# v1_2.net
KiCad netlist of a schematic drawn in EAGLE
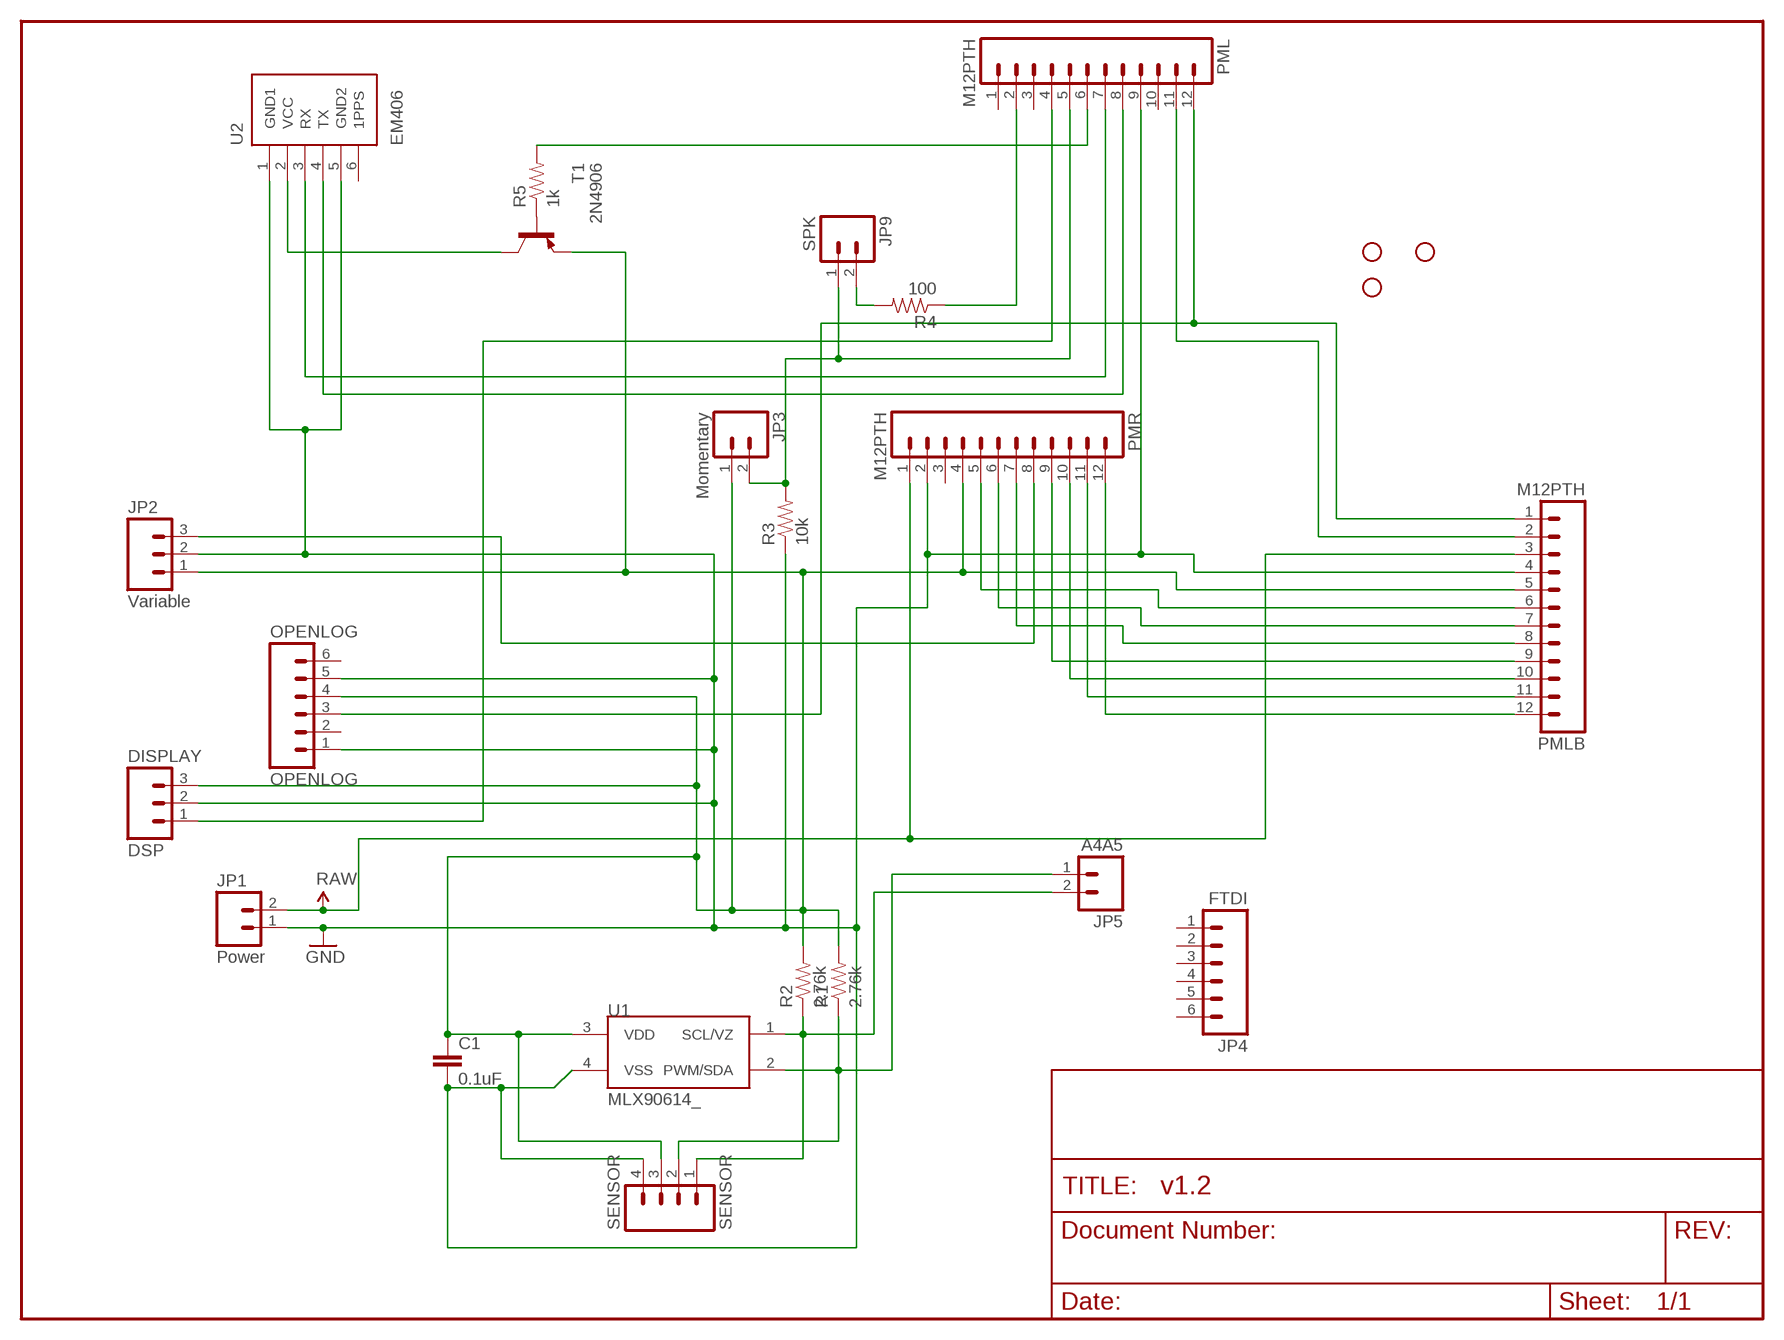
[diagram p0: schematic, sheet 1]

(export (version "E")
  (design (tool "Eeschema 10.0.6"))
  (components
    (comp (ref "2N4906")
      (value "T1")
      (footprint "eagle-import:TO92-EBC")
      (libsource (lib "eagle-import") (part "-PNP-TO92-EBC2N3906"))
    )
    (comp (ref "C1")
      (value "0.1uF")
      (footprint "eagle-import:CAP-PTH-LARGE")
      (libsource (lib "eagle-import") (part "CAPPTH3"))
    )
    (comp (ref "DISPLAY")
      (value "DSP")
      (footprint "eagle-import:SCREWTERMINAL-3.5MM-3_LOCK.007S")
      (libsource (lib "eagle-import") (part "M03SCREW_LOCK"))
    )
    (comp (ref "JP1")
      (value "Power")
      (footprint "eagle-import:JST-2-PTH")
      (libsource (lib "eagle-import") (part "M02JST-PTH-2"))
    )
    (comp (ref "JP2")
      (value "Variable")
      (footprint "eagle-import:SCREWTERMINAL-3.5MM-3_LOCK.007S")
      (libsource (lib "eagle-import") (part "M03SCREW_LOCK"))
    )
    (comp (ref "JP3")
      (value "Momentary")
      (footprint "eagle-import:JST-2-PTH")
      (libsource (lib "eagle-import") (part "M02JST-PTH-2"))
    )
    (comp (ref "JP4")
      (value "FTDI")
      (footprint "eagle-import:1X06")
      (libsource (lib "eagle-import") (part "M06SIP"))
    )
    (comp (ref "JP5")
      (value "A4A5")
      (footprint "eagle-import:1X02")
      (libsource (lib "eagle-import") (part "M02PTH"))
    )
    (comp (ref "JP6")
      (value "STAND-OFFTIGHT")
      (footprint "eagle-import:STAND-OFF-TIGHT")
      (libsource (lib "eagle-import") (part "STAND-OFFTIGHT"))
    )
    (comp (ref "JP7")
      (value "STAND-OFFTIGHT")
      (footprint "eagle-import:STAND-OFF-TIGHT")
      (libsource (lib "eagle-import") (part "STAND-OFFTIGHT"))
    )
    (comp (ref "JP8")
      (value "STAND-OFFTIGHT")
      (footprint "eagle-import:STAND-OFF-TIGHT")
      (libsource (lib "eagle-import") (part "STAND-OFFTIGHT"))
    )
    (comp (ref "JP9")
      (value "SPK")
      (footprint "eagle-import:SCREWTERMINAL-3.5MM-2")
      (libsource (lib "eagle-import") (part "M023.5MM"))
    )
    (comp (ref "OPENLOG")
      (value "OPENLOG")
      (footprint "eagle-import:1X06_LOCK")
      (libsource (lib "eagle-import") (part "M06LOCK"))
    )
    (comp (ref "PML")
      (value "M12PTH")
      (footprint "eagle-import:1X12")
      (libsource (lib "eagle-import") (part "M12PTH"))
    )
    (comp (ref "PMLB")
      (value "M12PTH")
      (footprint "eagle-import:1X12")
      (libsource (lib "eagle-import") (part "M12PTH"))
    )
    (comp (ref "PMR")
      (value "M12PTH")
      (footprint "eagle-import:1X12")
      (libsource (lib "eagle-import") (part "M12PTH"))
    )
    (comp (ref "R1")
      (value "2.76k")
      (footprint "eagle-import:AXIAL-0.4")
      (libsource (lib "eagle-import") (part "RESISTORPTH-1/4W"))
    )
    (comp (ref "R2")
      (value "2.76k")
      (footprint "eagle-import:AXIAL-0.4")
      (libsource (lib "eagle-import") (part "RESISTORPTH-1/4W"))
    )
    (comp (ref "R3")
      (value "10k")
      (footprint "eagle-import:AXIAL-0.4")
      (libsource (lib "eagle-import") (part "RESISTORPTH-1/4W"))
    )
    (comp (ref "R4")
      (value "100")
      (footprint "eagle-import:AXIAL-0.4")
      (libsource (lib "eagle-import") (part "RESISTORPTH-1/4W"))
    )
    (comp (ref "R5")
      (value "1k")
      (footprint "eagle-import:AXIAL-0.4")
      (libsource (lib "eagle-import") (part "RESISTORPTH-1/4W"))
    )
    (comp (ref "SENSOR")
      (value "SENSOR")
      (footprint "eagle-import:SCREWTERMINAL-3.5MM-4_LOCK")
      (libsource (lib "eagle-import") (part "M04SCREW_LOCK"))
    )
    (comp (ref "U1")
      (value "MLX90614_")
      (footprint "eagle-import:TO-39")
      (libsource (lib "eagle-import") (part "MLX90614_"))
    )
    (comp (ref "U2")
      (value "EM406")
      (footprint "eagle-import:EM406")
      (libsource (lib "eagle-import") (part "EM406"))
    )
  )
  (nets
    (net (code "1") (name "GND") (class "Default")
      (node (ref "C1") (pin "2") (pinfunction "2_2") (pintype "passive"))
      (node (ref "DISPLAY") (pin "2") (pinfunction "2_2") (pintype "passive"))
      (node (ref "JP1") (pin "1") (pinfunction "1_1") (pintype "passive"))
      (node (ref "JP2") (pin "2") (pinfunction "2_2") (pintype "passive"))
      (node (ref "OPENLOG") (pin "1") (pinfunction "1_1") (pintype "passive"))
      (node (ref "OPENLOG") (pin "5") (pinfunction "5_5") (pintype "passive"))
      (node (ref "PML") (pin "9") (pinfunction "9_9") (pintype "passive"))
      (node (ref "PMLB") (pin "4") (pinfunction "4_4") (pintype "passive"))
      (node (ref "PMR") (pin "2") (pinfunction "2_2") (pintype "passive"))
      (node (ref "R3") (pin "P$1") (pinfunction "1_P$1") (pintype "passive"))
      (node (ref "SENSOR") (pin "4") (pinfunction "4_4") (pintype "passive"))
      (node (ref "U1") (pin "4") (pinfunction "VSS_4") (pintype "bidirectional"))
      (node (ref "U2") (pin "1") (pinfunction "GND1_1") (pintype "bidirectional"))
      (node (ref "U2") (pin "5") (pinfunction "GND2_5") (pintype "bidirectional"))
    )
    (net (code "2") (name "Net-(DISPLAY-Pad1)") (class "Default")
      (node (ref "DISPLAY") (pin "1") (pinfunction "1_1") (pintype "passive"))
      (node (ref "PML") (pin "4") (pinfunction "4_4") (pintype "passive"))
    )
    (net (code "3") (name "Net-(JP2-Pad3)") (class "Default")
      (node (ref "JP2") (pin "3") (pinfunction "3_3") (pintype "passive"))
      (node (ref "PMR") (pin "8") (pinfunction "8_8") (pintype "passive"))
    )
    (net (code "4") (name "Net-(OPENLOG-Pad3)") (class "Default")
      (node (ref "OPENLOG") (pin "3") (pinfunction "3_3") (pintype "passive"))
      (node (ref "PML") (pin "12") (pinfunction "12_12") (pintype "passive"))
      (node (ref "PMLB") (pin "1") (pinfunction "1_1") (pintype "passive"))
    )
    (net (code "5") (name "Net-(PML-Pad11)") (class "Default")
      (node (ref "PML") (pin "11") (pinfunction "11_11") (pintype "passive"))
      (node (ref "PMLB") (pin "2") (pinfunction "2_2") (pintype "passive"))
    )
    (net (code "6") (name "Net-(PMLB-Pad6)") (class "Default")
      (node (ref "PMLB") (pin "6") (pinfunction "6_6") (pintype "passive"))
      (node (ref "PMR") (pin "5") (pinfunction "5_5") (pintype "passive"))
    )
    (net (code "7") (name "Net-(PMLB-Pad7)") (class "Default")
      (node (ref "PMLB") (pin "7") (pinfunction "7_7") (pintype "passive"))
      (node (ref "PMR") (pin "6") (pinfunction "6_6") (pintype "passive"))
    )
    (net (code "8") (name "Net-(PMLB-Pad8)") (class "Default")
      (node (ref "PMLB") (pin "8") (pinfunction "8_8") (pintype "passive"))
      (node (ref "PMR") (pin "7") (pinfunction "7_7") (pintype "passive"))
    )
    (net (code "9") (name "Net-(PMLB-Pad9)") (class "Default")
      (node (ref "PMLB") (pin "9") (pinfunction "9_9") (pintype "passive"))
      (node (ref "PMR") (pin "9") (pinfunction "9_9") (pintype "passive"))
    )
    (net (code "10") (name "Net-(PMLB-Pad10)") (class "Default")
      (node (ref "PMLB") (pin "10") (pinfunction "10_10") (pintype "passive"))
      (node (ref "PMR") (pin "10") (pinfunction "10_10") (pintype "passive"))
    )
    (net (code "11") (name "Net-(PMLB-Pad11)") (class "Default")
      (node (ref "PMLB") (pin "11") (pinfunction "11_11") (pintype "passive"))
      (node (ref "PMR") (pin "11") (pinfunction "11_11") (pintype "passive"))
    )
    (net (code "12") (name "Net-(PMLB-Pad12)") (class "Default")
      (node (ref "PMLB") (pin "12") (pinfunction "12_12") (pintype "passive"))
      (node (ref "PMR") (pin "12") (pinfunction "12_12") (pintype "passive"))
    )
    (net (code "13") (name "Net-(R1-1)") (class "Default")
      (node (ref "JP5") (pin "1") (pinfunction "1_1") (pintype "passive"))
      (node (ref "R1") (pin "P$1") (pinfunction "1_P$1") (pintype "passive"))
      (node (ref "SENSOR") (pin "2") (pinfunction "2_2") (pintype "passive"))
      (node (ref "U1") (pin "2") (pinfunction "PWM/SDA_2") (pintype "bidirectional"))
    )
    (net (code "14") (name "Net-(R1-2)") (class "Default")
      (node (ref "2N4906") (pin "E") (pinfunction "E_E") (pintype "passive"))
      (node (ref "C1") (pin "1") (pinfunction "1_1") (pintype "passive"))
      (node (ref "DISPLAY") (pin "3") (pinfunction "3_3") (pintype "passive"))
      (node (ref "JP2") (pin "1") (pinfunction "1_1") (pintype "passive"))
      (node (ref "JP3") (pin "1") (pinfunction "1_1") (pintype "passive"))
      (node (ref "OPENLOG") (pin "4") (pinfunction "4_4") (pintype "passive"))
      (node (ref "PMLB") (pin "5") (pinfunction "5_5") (pintype "passive"))
      (node (ref "PMR") (pin "4") (pinfunction "4_4") (pintype "passive"))
      (node (ref "R1") (pin "P$2") (pinfunction "2_P$2") (pintype "passive"))
      (node (ref "R2") (pin "P$2") (pinfunction "2_P$2") (pintype "passive"))
      (node (ref "SENSOR") (pin "3") (pinfunction "3_3") (pintype "passive"))
      (node (ref "U1") (pin "3") (pinfunction "VDD_3") (pintype "bidirectional"))
    )
    (net (code "15") (name "Net-(R2-1)") (class "Default")
      (node (ref "JP5") (pin "2") (pinfunction "2_2") (pintype "passive"))
      (node (ref "R2") (pin "P$1") (pinfunction "1_P$1") (pintype "passive"))
      (node (ref "SENSOR") (pin "1") (pinfunction "1_1") (pintype "passive"))
      (node (ref "U1") (pin "1") (pinfunction "SCL/VZ_1") (pintype "bidirectional"))
    )
    (net (code "16") (name "Net-(R3-2)") (class "Default")
      (node (ref "JP3") (pin "2") (pinfunction "2_2") (pintype "passive"))
      (node (ref "JP9") (pin "1") (pinfunction "1_1") (pintype "passive"))
      (node (ref "PML") (pin "5") (pinfunction "5_5") (pintype "passive"))
      (node (ref "R3") (pin "P$2") (pinfunction "2_P$2") (pintype "passive"))
    )
    (net (code "17") (name "Net-(R4-1)") (class "Default")
      (node (ref "PML") (pin "2") (pinfunction "2_2") (pintype "passive"))
      (node (ref "R4") (pin "P$1") (pinfunction "1_P$1") (pintype "passive"))
    )
    (net (code "18") (name "Net-(R4-2)") (class "Default")
      (node (ref "JP9") (pin "2") (pinfunction "2_2") (pintype "passive"))
      (node (ref "R4") (pin "P$2") (pinfunction "2_P$2") (pintype "passive"))
    )
    (net (code "19") (name "Net-(R5-1)") (class "Default")
      (node (ref "2N4906") (pin "B") (pinfunction "B_B") (pintype "passive"))
      (node (ref "R5") (pin "P$1") (pinfunction "1_P$1") (pintype "passive"))
    )
    (net (code "20") (name "Net-(R5-2)") (class "Default")
      (node (ref "PML") (pin "6") (pinfunction "6_6") (pintype "passive"))
      (node (ref "R5") (pin "P$2") (pinfunction "2_P$2") (pintype "passive"))
    )
    (net (code "21") (name "Net-(U2-RX)") (class "Default")
      (node (ref "PML") (pin "7") (pinfunction "7_7") (pintype "passive"))
      (node (ref "U2") (pin "3") (pinfunction "RX_3") (pintype "bidirectional"))
    )
    (net (code "22") (name "Net-(U2-TX)") (class "Default")
      (node (ref "PML") (pin "8") (pinfunction "8_8") (pintype "passive"))
      (node (ref "U2") (pin "4") (pinfunction "TX_4") (pintype "bidirectional"))
    )
    (net (code "23") (name "Net-(U2-VCC)") (class "Default")
      (node (ref "2N4906") (pin "C") (pinfunction "C_C") (pintype "passive"))
      (node (ref "U2") (pin "2") (pinfunction "VCC_2") (pintype "bidirectional"))
    )
    (net (code "24") (name "RAW") (class "Default")
      (node (ref "JP1") (pin "2") (pinfunction "2_2") (pintype "passive"))
      (node (ref "PMLB") (pin "3") (pinfunction "3_3") (pintype "passive"))
      (node (ref "PMR") (pin "1") (pinfunction "1_1") (pintype "passive"))
    )
    (net (code "25") (name "unconnected-(JP4-Pad1)") (class "Default")
      (node (ref "JP4") (pin "1") (pinfunction "1_1") (pintype "passive"))
    )
    (net (code "26") (name "unconnected-(JP4-Pad2)") (class "Default")
      (node (ref "JP4") (pin "2") (pinfunction "2_2") (pintype "passive"))
    )
    (net (code "27") (name "unconnected-(JP4-Pad3)") (class "Default")
      (node (ref "JP4") (pin "3") (pinfunction "3_3") (pintype "passive"))
    )
    (net (code "28") (name "unconnected-(JP4-Pad4)") (class "Default")
      (node (ref "JP4") (pin "4") (pinfunction "4_4") (pintype "passive"))
    )
    (net (code "29") (name "unconnected-(JP4-Pad5)") (class "Default")
      (node (ref "JP4") (pin "5") (pinfunction "5_5") (pintype "passive"))
    )
    (net (code "30") (name "unconnected-(JP4-Pad6)") (class "Default")
      (node (ref "JP4") (pin "6") (pinfunction "6_6") (pintype "passive"))
    )
    (net (code "31") (name "unconnected-(OPENLOG-Pad2)") (class "Default")
      (node (ref "OPENLOG") (pin "2") (pinfunction "2_2") (pintype "passive"))
    )
    (net (code "32") (name "unconnected-(OPENLOG-Pad6)") (class "Default")
      (node (ref "OPENLOG") (pin "6") (pinfunction "6_6") (pintype "passive"))
    )
    (net (code "33") (name "unconnected-(PML-Pad1)") (class "Default")
      (node (ref "PML") (pin "1") (pinfunction "1_1") (pintype "passive"))
    )
    (net (code "34") (name "unconnected-(PML-Pad3)") (class "Default")
      (node (ref "PML") (pin "3") (pinfunction "3_3") (pintype "passive"))
    )
    (net (code "35") (name "unconnected-(PML-Pad10)") (class "Default")
      (node (ref "PML") (pin "10") (pinfunction "10_10") (pintype "passive"))
    )
    (net (code "36") (name "unconnected-(PMR-Pad3)") (class "Default")
      (node (ref "PMR") (pin "3") (pinfunction "3_3") (pintype "passive"))
    )
    (net (code "37") (name "unconnected-(U2-1PPS-Pad6)") (class "Default")
      (node (ref "U2") (pin "6") (pinfunction "1PPS_6") (pintype "bidirectional"))
    )
  )
)
